# 20240311-sn76489-ver1.net
KiCad netlist of a schematic drawn in EAGLE
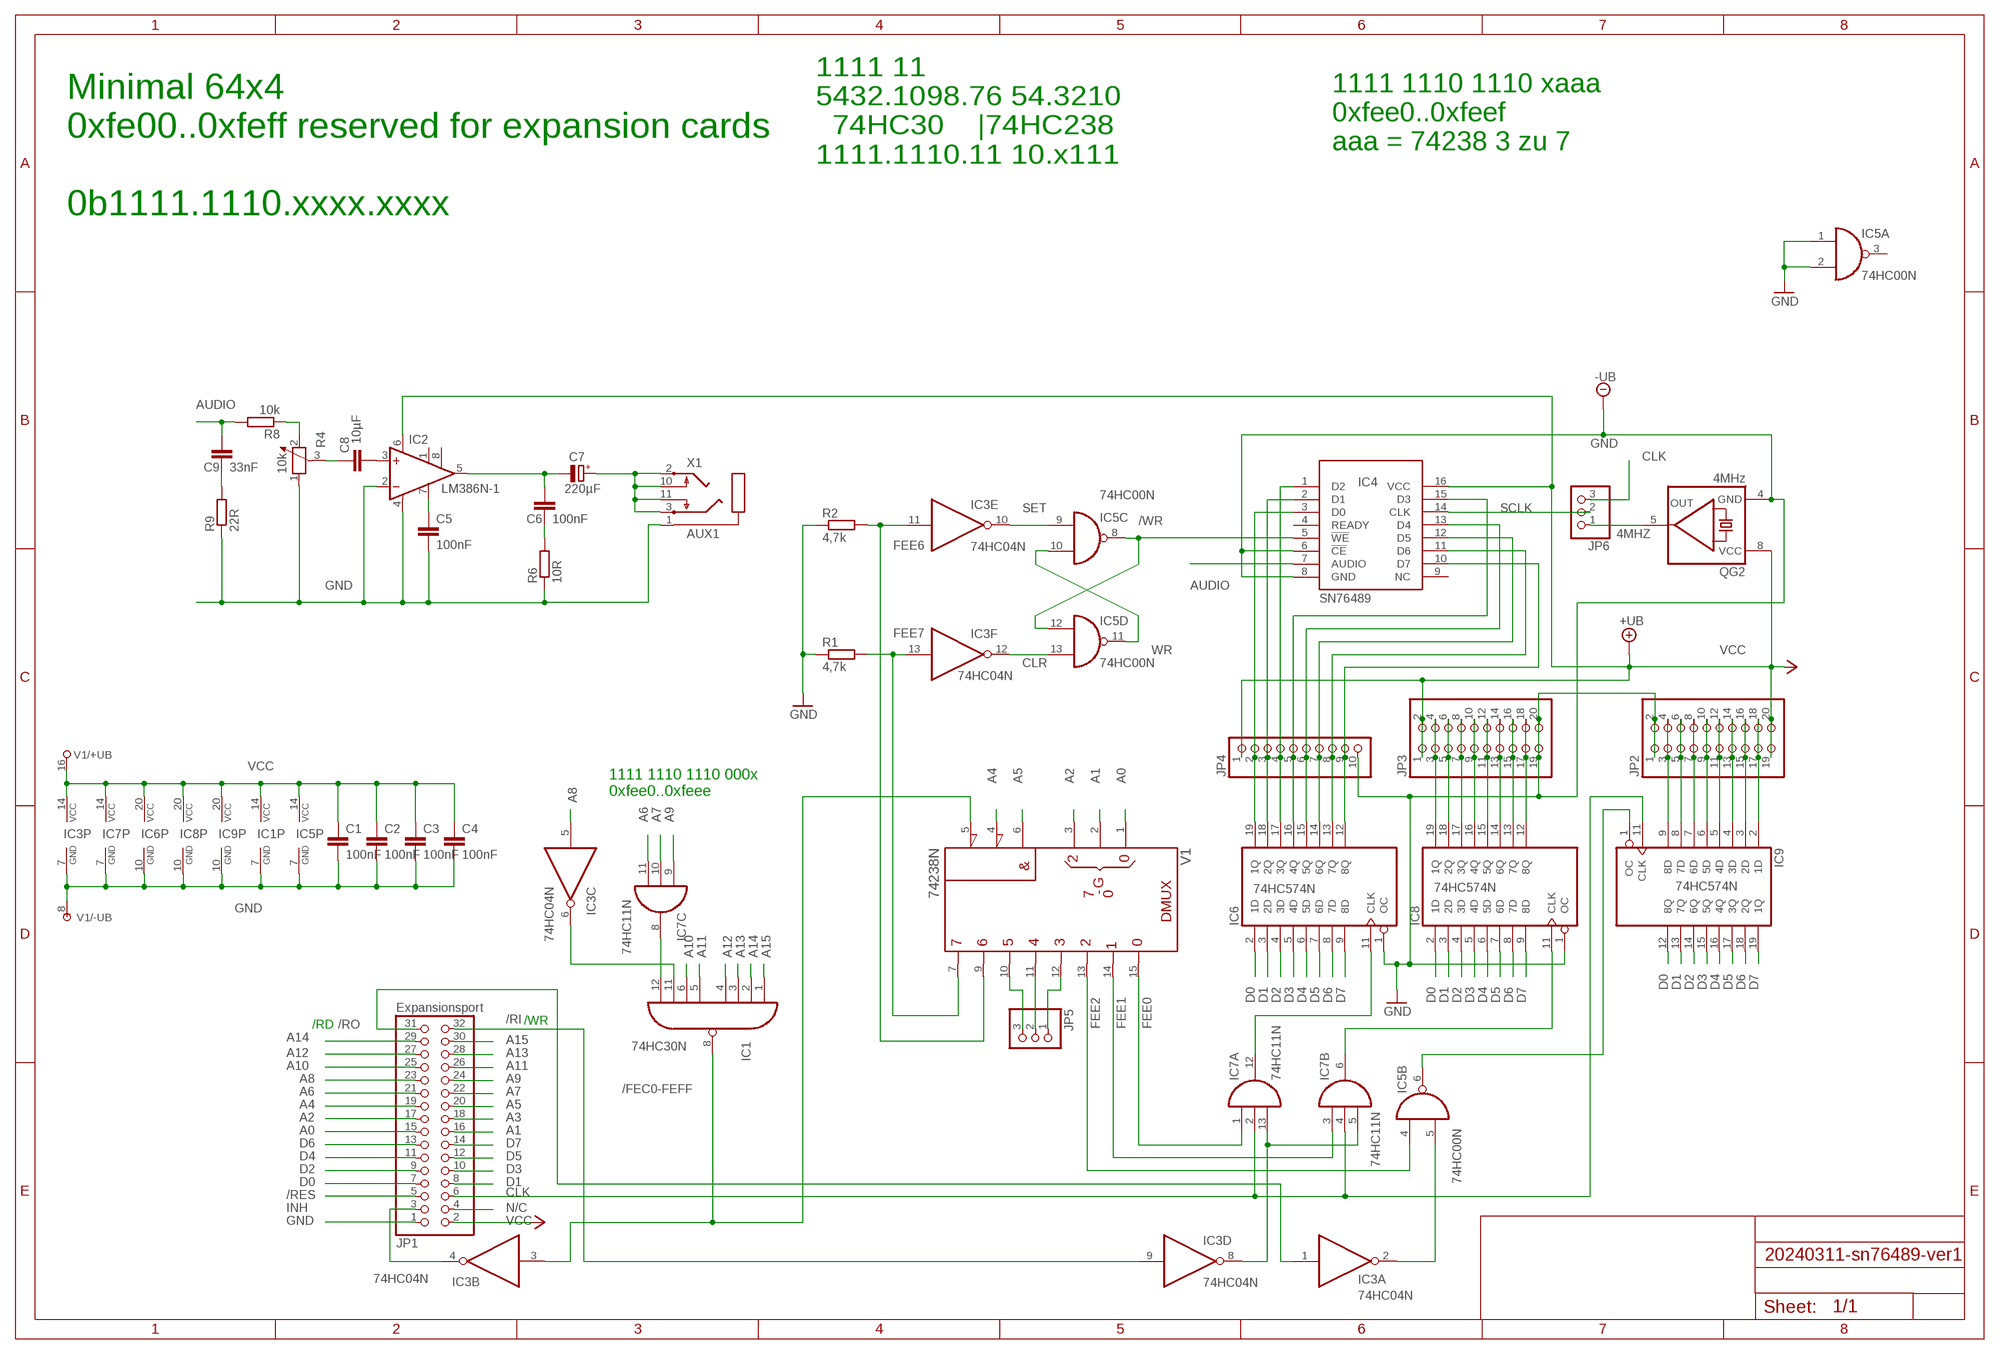
[diagram p0: schematic, sheet 1]

(export (version "E")
  (design (tool "Eeschema 10.0.6"))
  (components
    (comp (ref "C1")
      (value "100nF")
      (footprint "eagle-import:C050-025X075")
      (libsource (lib "eagle-import") (part "C-EU050-025X075"))
    )
    (comp (ref "C2")
      (value "100nF")
      (footprint "eagle-import:C050-025X075")
      (libsource (lib "eagle-import") (part "C-EU050-025X075"))
    )
    (comp (ref "C3")
      (value "100nF")
      (footprint "eagle-import:C050-025X075")
      (libsource (lib "eagle-import") (part "C-EU050-025X075"))
    )
    (comp (ref "C4")
      (value "100nF")
      (footprint "eagle-import:C050-025X075")
      (libsource (lib "eagle-import") (part "C-EU050-025X075"))
    )
    (comp (ref "C5")
      (value "100nF")
      (footprint "eagle-import:C050-025X075")
      (libsource (lib "eagle-import") (part "C-EU050-025X075"))
    )
    (comp (ref "C6")
      (value "100nF")
      (footprint "eagle-import:C050-025X075")
      (libsource (lib "eagle-import") (part "C-EU050-025X075"))
    )
    (comp (ref "C7")
      (value "220µF")
      (footprint "eagle-import:E2,5-7")
      (libsource (lib "eagle-import") (part "CPOL-EUE2.5-7"))
    )
    (comp (ref "C8")
      (value "10µF")
      (footprint "eagle-import:C050-025X075")
      (libsource (lib "eagle-import") (part "C-EU050-025X075"))
    )
    (comp (ref "C9")
      (value "33nF")
      (footprint "eagle-import:C050-025X075")
      (libsource (lib "eagle-import") (part "C-EU050-025X075"))
    )
    (comp (ref "IC1")
      (value "74HC30N")
      (footprint "eagle-import:DIL14")
      (libsource (lib "eagle-import") (part "7430NHC"))
    )
    (comp (ref "IC2")
      (value "LM386N-1")
      (footprint "eagle-import:DIL08")
      (libsource (lib "eagle-import") (part "LM386?-N1"))
    )
    (comp (ref "IC3")
      (value "74HC04N")
      (footprint "eagle-import:DIL14")
      (libsource (lib "eagle-import") (part "7404NHC"))
    )
    (comp (ref "IC4")
      (value "SN76489")
      (footprint "eagle-import:ALEX-PARTS_DIL16")
      (libsource (lib "eagle-import") (part "ALEX-PARTS_SN76489AN"))
    )
    (comp (ref "IC5")
      (value "74HC00N")
      (footprint "eagle-import:DIL14")
      (libsource (lib "eagle-import") (part "7400NHC"))
    )
    (comp (ref "IC6")
      (value "74HC574N")
      (footprint "eagle-import:DIL20")
      (libsource (lib "eagle-import") (part "74574NHC"))
    )
    (comp (ref "IC7")
      (value "74HC11N")
      (footprint "eagle-import:DIL14")
      (libsource (lib "eagle-import") (part "7411NHC"))
    )
    (comp (ref "IC8")
      (value "74HC574N")
      (footprint "eagle-import:DIL20")
      (libsource (lib "eagle-import") (part "74574NHC"))
    )
    (comp (ref "IC9")
      (value "74HC574N")
      (footprint "eagle-import:DIL20")
      (libsource (lib "eagle-import") (part "74574NHC"))
    )
    (comp (ref "JP1")
      (value "Expansionsport")
      (footprint "eagle-import:2X16")
      (libsource (lib "eagle-import") (part "PINHD-2X16"))
    )
    (comp (ref "JP2")
      (value "PINHD-2X10")
      (footprint "eagle-import:2X10")
      (libsource (lib "eagle-import") (part "PINHD-2X10"))
    )
    (comp (ref "JP3")
      (value "PINHD-2X10")
      (footprint "eagle-import:2X10")
      (libsource (lib "eagle-import") (part "PINHD-2X10"))
    )
    (comp (ref "JP4")
      (value "PINHD-1X10")
      (footprint "eagle-import:1X10")
      (libsource (lib "eagle-import") (part "PINHD-1X10"))
    )
    (comp (ref "JP5")
      (value "PINHD-1X3")
      (footprint "eagle-import:1X03")
      (libsource (lib "eagle-import") (part "PINHD-1X3"))
    )
    (comp (ref "JP6")
      (value "PINHD-1X3")
      (footprint "eagle-import:1X03")
      (libsource (lib "eagle-import") (part "PINHD-1X3"))
    )
    (comp (ref "QG2")
      (value "4MHz")
      (footprint "eagle-import:DIL08S")
      (libsource (lib "eagle-import") (part "QG5460"))
    )
    (comp (ref "R1")
      (value "4,7k")
      (footprint "eagle-import:0207_10")
      (libsource (lib "eagle-import") (part "R-EU_0207/10"))
    )
    (comp (ref "R2")
      (value "4,7k")
      (footprint "eagle-import:0207_10")
      (libsource (lib "eagle-import") (part "R-EU_0207/10"))
    )
    (comp (ref "R4")
      (value "10k")
      (footprint "eagle-import:PT-10S")
      (libsource (lib "eagle-import") (part "POTENTIOMETER_PT-10S"))
    )
    (comp (ref "R6")
      (value "10R")
      (footprint "eagle-import:0207_10")
      (libsource (lib "eagle-import") (part "R-EU_0207/10"))
    )
    (comp (ref "R8")
      (value "10k")
      (footprint "eagle-import:0207_10")
      (libsource (lib "eagle-import") (part "R-EU_0207/10"))
    )
    (comp (ref "R9")
      (value "22R")
      (footprint "eagle-import:0207_10")
      (libsource (lib "eagle-import") (part "R-EU_0207/10"))
    )
    (comp (ref "V1")
      (value "74238N")
      (footprint "eagle-import:DIL16")
      (libsource (lib "eagle-import") (part "74238N"))
    )
    (comp (ref "X1")
      (value "AUX1")
      (footprint "eagle-import:SJ1-352XN")
      (libsource (lib "eagle-import") (part "CON-SJ1-352XNSJ1-352XN"))
    )
  )
  (nets
    (net (code "1") (name "+UB") (class "Default")
      (node (ref "C1") (pin "1") (pinfunction "1_1") (pintype "passive"))
      (node (ref "C2") (pin "1") (pinfunction "1_1") (pintype "passive"))
      (node (ref "C3") (pin "1") (pinfunction "1_1") (pintype "passive"))
      (node (ref "C4") (pin "1") (pinfunction "1_1") (pintype "passive"))
      (node (ref "IC1") (pin "14") (pinfunction "VCC_14") (pintype "power_in"))
      (node (ref "IC2") (pin "6") (pinfunction "VS_6") (pintype "power_in"))
      (node (ref "IC3") (pin "14") (pinfunction "VCC_14") (pintype "power_in"))
      (node (ref "IC4") (pin "16") (pinfunction "VCC_16") (pintype "input"))
      (node (ref "IC5") (pin "14") (pinfunction "VCC_14") (pintype "power_in"))
      (node (ref "IC6") (pin "20") (pinfunction "VCC_20") (pintype "power_in"))
      (node (ref "IC7") (pin "14") (pinfunction "VCC_14") (pintype "power_in"))
      (node (ref "IC8") (pin "20") (pinfunction "VCC_20") (pintype "power_in"))
      (node (ref "IC9") (pin "20") (pinfunction "VCC_20") (pintype "power_in"))
      (node (ref "JP1") (pin "2") (pinfunction "2_2") (pintype "passive"))
      (node (ref "JP2") (pin "19") (pinfunction "19_19") (pintype "passive"))
      (node (ref "JP2") (pin "20") (pinfunction "20_20") (pintype "passive"))
      (node (ref "JP3") (pin "1") (pinfunction "1_1") (pintype "passive"))
      (node (ref "JP3") (pin "2") (pinfunction "2_2") (pintype "passive"))
      (node (ref "JP4") (pin "1") (pinfunction "1_1") (pintype "passive"))
      (node (ref "QG2") (pin "8") (pinfunction "VCC_8") (pintype "power_in"))
      (node (ref "V1") (pin "16") (pinfunction "+UB_16") (pintype "power_in"))
    )
    (net (code "2") (name "-UB") (class "Default")
      (node (ref "C1") (pin "2") (pinfunction "2_2") (pintype "passive"))
      (node (ref "C2") (pin "2") (pinfunction "2_2") (pintype "passive"))
      (node (ref "C3") (pin "2") (pinfunction "2_2") (pintype "passive"))
      (node (ref "C4") (pin "2") (pinfunction "2_2") (pintype "passive"))
      (node (ref "C5") (pin "2") (pinfunction "2_2") (pintype "passive"))
      (node (ref "IC1") (pin "7") (pinfunction "GND_7") (pintype "power_in"))
      (node (ref "IC2") (pin "2") (pinfunction "-IN_2") (pintype "input"))
      (node (ref "IC2") (pin "4") (pinfunction "GND_4") (pintype "power_in"))
      (node (ref "IC3") (pin "7") (pinfunction "GND_7") (pintype "power_in"))
      (node (ref "IC4") (pin "6") (pinfunction "~{CE}_6") (pintype "input"))
      (node (ref "IC4") (pin "8") (pinfunction "GND_8") (pintype "power_in"))
      (node (ref "IC5") (pin "1") (pinfunction "I0_1") (pintype "input"))
      (node (ref "IC5") (pin "2") (pinfunction "I1_2") (pintype "input"))
      (node (ref "IC5") (pin "7") (pinfunction "GND_7") (pintype "power_in"))
      (node (ref "IC6") (pin "1") (pinfunction "OC_1") (pintype "input"))
      (node (ref "IC6") (pin "10") (pinfunction "GND_10") (pintype "power_in"))
      (node (ref "IC7") (pin "7") (pinfunction "GND_7") (pintype "power_in"))
      (node (ref "IC8") (pin "1") (pinfunction "OC_1") (pintype "input"))
      (node (ref "IC8") (pin "10") (pinfunction "GND_10") (pintype "power_in"))
      (node (ref "IC9") (pin "10") (pinfunction "GND_10") (pintype "power_in"))
      (node (ref "JP1") (pin "1") (pinfunction "1_1") (pintype "passive"))
      (node (ref "JP2") (pin "1") (pinfunction "1_1") (pintype "passive"))
      (node (ref "JP2") (pin "2") (pinfunction "2_2") (pintype "passive"))
      (node (ref "JP3") (pin "19") (pinfunction "19_19") (pintype "passive"))
      (node (ref "JP3") (pin "20") (pinfunction "20_20") (pintype "passive"))
      (node (ref "JP4") (pin "10") (pinfunction "10_10") (pintype "passive"))
      (node (ref "QG2") (pin "4") (pinfunction "GND_4") (pintype "power_in"))
      (node (ref "R1") (pin "1") (pinfunction "1_1") (pintype "passive"))
      (node (ref "R2") (pin "1") (pinfunction "1_1") (pintype "passive"))
      (node (ref "R4") (pin "1") (pinfunction "1_1") (pintype "passive"))
      (node (ref "R6") (pin "1") (pinfunction "1_1") (pintype "passive"))
      (node (ref "R9") (pin "1") (pinfunction "1_1") (pintype "passive"))
      (node (ref "V1") (pin "8") (pinfunction "-UB_8") (pintype "power_in"))
      (node (ref "X1") (pin "1") (pinfunction "1_1") (pintype "passive"))
    )
    (net (code "3") (name "/4MHZ") (class "Default")
      (node (ref "JP6") (pin "1") (pinfunction "1_1") (pintype "passive"))
      (node (ref "QG2") (pin "5") (pinfunction "OUT_5") (pintype "output"))
    )
    (net (code "4") (name "/A0") (class "Default")
      (node (ref "JP1") (pin "15") (pinfunction "15_15") (pintype "passive"))
      (node (ref "V1") (pin "1") (pinfunction "A_1") (pintype "input"))
    )
    (net (code "5") (name "/A1") (class "Default")
      (node (ref "JP1") (pin "16") (pinfunction "16_16") (pintype "passive"))
      (node (ref "V1") (pin "2") (pinfunction "B_2") (pintype "input"))
    )
    (net (code "6") (name "/A2") (class "Default")
      (node (ref "JP1") (pin "17") (pinfunction "17_17") (pintype "passive"))
      (node (ref "V1") (pin "3") (pinfunction "C_3") (pintype "input"))
    )
    (net (code "7") (name "/A3") (class "Default")
      (node (ref "JP1") (pin "18") (pinfunction "18_18") (pintype "passive"))
    )
    (net (code "8") (name "/A4") (class "Default")
      (node (ref "JP1") (pin "19") (pinfunction "19_19") (pintype "passive"))
      (node (ref "V1") (pin "4") (pinfunction "~{G2A}_4") (pintype "input"))
    )
    (net (code "9") (name "/A5") (class "Default")
      (node (ref "JP1") (pin "20") (pinfunction "20_20") (pintype "passive"))
      (node (ref "V1") (pin "6") (pinfunction "G1_6") (pintype "input"))
    )
    (net (code "10") (name "/A6") (class "Default")
      (node (ref "IC7") (pin "11") (pinfunction "I2_11") (pintype "input"))
      (node (ref "JP1") (pin "21") (pinfunction "21_21") (pintype "passive"))
    )
    (net (code "11") (name "/A7") (class "Default")
      (node (ref "IC7") (pin "10") (pinfunction "I1_10") (pintype "input"))
      (node (ref "JP1") (pin "22") (pinfunction "22_22") (pintype "passive"))
    )
    (net (code "12") (name "/A8") (class "Default")
      (node (ref "IC3") (pin "5") (pinfunction "I_5") (pintype "input"))
      (node (ref "JP1") (pin "23") (pinfunction "23_23") (pintype "passive"))
    )
    (net (code "13") (name "/A9") (class "Default")
      (node (ref "IC7") (pin "9") (pinfunction "I0_9") (pintype "input"))
      (node (ref "JP1") (pin "24") (pinfunction "24_24") (pintype "passive"))
    )
    (net (code "14") (name "/A10") (class "Default")
      (node (ref "IC1") (pin "6") (pinfunction "I5_6") (pintype "input"))
      (node (ref "JP1") (pin "25") (pinfunction "25_25") (pintype "passive"))
    )
    (net (code "15") (name "/A11") (class "Default")
      (node (ref "IC1") (pin "5") (pinfunction "I4_5") (pintype "input"))
      (node (ref "JP1") (pin "26") (pinfunction "26_26") (pintype "passive"))
    )
    (net (code "16") (name "/A12") (class "Default")
      (node (ref "IC1") (pin "4") (pinfunction "I3_4") (pintype "input"))
      (node (ref "JP1") (pin "27") (pinfunction "27_27") (pintype "passive"))
    )
    (net (code "17") (name "/A13") (class "Default")
      (node (ref "IC1") (pin "3") (pinfunction "I2_3") (pintype "input"))
      (node (ref "JP1") (pin "28") (pinfunction "28_28") (pintype "passive"))
    )
    (net (code "18") (name "/A14") (class "Default")
      (node (ref "IC1") (pin "2") (pinfunction "I1_2") (pintype "input"))
      (node (ref "JP1") (pin "29") (pinfunction "29_29") (pintype "passive"))
    )
    (net (code "19") (name "/A15") (class "Default")
      (node (ref "IC1") (pin "1") (pinfunction "I0_1") (pintype "input"))
      (node (ref "JP1") (pin "30") (pinfunction "30_30") (pintype "passive"))
    )
    (net (code "20") (name "/AUDIO") (class "Default")
      (node (ref "C9") (pin "1") (pinfunction "1_1") (pintype "passive"))
      (node (ref "IC4") (pin "7") (pinfunction "AUDIO_7") (pintype "output"))
      (node (ref "R8") (pin "2") (pinfunction "2_2") (pintype "passive"))
    )
    (net (code "21") (name "/CLK") (class "Default")
      (node (ref "IC7") (pin "2") (pinfunction "I1_2") (pintype "input"))
      (node (ref "IC7") (pin "4") (pinfunction "I1_4") (pintype "input"))
      (node (ref "IC9") (pin "11") (pinfunction "CLK_11") (pintype "input"))
      (node (ref "JP1") (pin "6") (pinfunction "6_6") (pintype "passive"))
      (node (ref "JP6") (pin "3") (pinfunction "3_3") (pintype "passive"))
    )
    (net (code "22") (name "/CLR") (class "Default")
      (node (ref "IC3") (pin "12") (pinfunction "O_12") (pintype "output"))
      (node (ref "IC5") (pin "13") (pinfunction "I1_13") (pintype "input"))
    )
    (net (code "23") (name "/D0") (class "Default")
      (node (ref "IC6") (pin "2") (pinfunction "1D_2") (pintype "input"))
      (node (ref "IC8") (pin "2") (pinfunction "1D_2") (pintype "input"))
      (node (ref "IC9") (pin "12") (pinfunction "8Q_12") (pintype "tri_state"))
      (node (ref "JP1") (pin "7") (pinfunction "7_7") (pintype "passive"))
    )
    (net (code "24") (name "/D1") (class "Default")
      (node (ref "IC6") (pin "3") (pinfunction "2D_3") (pintype "input"))
      (node (ref "IC8") (pin "3") (pinfunction "2D_3") (pintype "input"))
      (node (ref "IC9") (pin "13") (pinfunction "7Q_13") (pintype "tri_state"))
      (node (ref "JP1") (pin "8") (pinfunction "8_8") (pintype "passive"))
    )
    (net (code "25") (name "/D2") (class "Default")
      (node (ref "IC6") (pin "4") (pinfunction "3D_4") (pintype "input"))
      (node (ref "IC8") (pin "4") (pinfunction "3D_4") (pintype "input"))
      (node (ref "IC9") (pin "14") (pinfunction "6Q_14") (pintype "tri_state"))
      (node (ref "JP1") (pin "9") (pinfunction "9_9") (pintype "passive"))
    )
    (net (code "26") (name "/D3") (class "Default")
      (node (ref "IC6") (pin "5") (pinfunction "4D_5") (pintype "input"))
      (node (ref "IC8") (pin "5") (pinfunction "4D_5") (pintype "input"))
      (node (ref "IC9") (pin "15") (pinfunction "5Q_15") (pintype "tri_state"))
      (node (ref "JP1") (pin "10") (pinfunction "10_10") (pintype "passive"))
    )
    (net (code "27") (name "/D4") (class "Default")
      (node (ref "IC6") (pin "6") (pinfunction "5D_6") (pintype "input"))
      (node (ref "IC8") (pin "6") (pinfunction "5D_6") (pintype "input"))
      (node (ref "IC9") (pin "16") (pinfunction "4Q_16") (pintype "tri_state"))
      (node (ref "JP1") (pin "11") (pinfunction "11_11") (pintype "passive"))
    )
    (net (code "28") (name "/D5") (class "Default")
      (node (ref "IC6") (pin "7") (pinfunction "6D_7") (pintype "input"))
      (node (ref "IC8") (pin "7") (pinfunction "6D_7") (pintype "input"))
      (node (ref "IC9") (pin "17") (pinfunction "3Q_17") (pintype "tri_state"))
      (node (ref "JP1") (pin "12") (pinfunction "12_12") (pintype "passive"))
    )
    (net (code "29") (name "/D6") (class "Default")
      (node (ref "IC6") (pin "8") (pinfunction "7D_8") (pintype "input"))
      (node (ref "IC8") (pin "8") (pinfunction "7D_8") (pintype "input"))
      (node (ref "IC9") (pin "18") (pinfunction "2Q_18") (pintype "tri_state"))
      (node (ref "JP1") (pin "13") (pinfunction "13_13") (pintype "passive"))
    )
    (net (code "30") (name "/D7") (class "Default")
      (node (ref "IC6") (pin "9") (pinfunction "8D_9") (pintype "input"))
      (node (ref "IC8") (pin "9") (pinfunction "8D_9") (pintype "input"))
      (node (ref "IC9") (pin "19") (pinfunction "1Q_19") (pintype "tri_state"))
      (node (ref "JP1") (pin "14") (pinfunction "14_14") (pintype "passive"))
    )
    (net (code "31") (name "/FEE0") (class "Default")
      (node (ref "IC7") (pin "1") (pinfunction "I0_1") (pintype "input"))
      (node (ref "V1") (pin "15") (pinfunction "Y0_15") (pintype "output"))
    )
    (net (code "32") (name "/FEE1") (class "Default")
      (node (ref "IC7") (pin "3") (pinfunction "I0_3") (pintype "input"))
      (node (ref "V1") (pin "14") (pinfunction "Y1_14") (pintype "output"))
    )
    (net (code "33") (name "/FEE2") (class "Default")
      (node (ref "IC5") (pin "4") (pinfunction "I0_4") (pintype "input"))
      (node (ref "V1") (pin "13") (pinfunction "Y2_13") (pintype "output"))
    )
    (net (code "34") (name "/FEE6") (class "Default")
      (node (ref "IC3") (pin "11") (pinfunction "I_11") (pintype "input"))
      (node (ref "R2") (pin "2") (pinfunction "2_2") (pintype "passive"))
      (node (ref "V1") (pin "9") (pinfunction "Y6_9") (pintype "output"))
    )
    (net (code "35") (name "/FEE7") (class "Default")
      (node (ref "IC3") (pin "13") (pinfunction "I_13") (pintype "input"))
      (node (ref "R1") (pin "2") (pinfunction "2_2") (pintype "passive"))
      (node (ref "V1") (pin "7") (pinfunction "Y7_7") (pintype "output"))
    )
    (net (code "36") (name "/INH") (class "Default")
      (node (ref "IC3") (pin "4") (pinfunction "O_4") (pintype "output"))
      (node (ref "JP1") (pin "3") (pinfunction "3_3") (pintype "passive"))
    )
    (net (code "37") (name "/N{slash}C") (class "Default")
      (node (ref "JP1") (pin "4") (pinfunction "4_4") (pintype "passive"))
    )
    (net (code "38") (name "/SCLK") (class "Default")
      (node (ref "IC4") (pin "14") (pinfunction "CLK_14") (pintype "input"))
      (node (ref "JP6") (pin "2") (pinfunction "2_2") (pintype "passive"))
    )
    (net (code "39") (name "/SET") (class "Default")
      (node (ref "IC3") (pin "10") (pinfunction "O_10") (pintype "output"))
      (node (ref "IC5") (pin "9") (pinfunction "I0_9") (pintype "input"))
    )
    (net (code "40") (name "/WR") (class "Default")
      (node (ref "IC5") (pin "10") (pinfunction "I1_10") (pintype "input"))
      (node (ref "IC5") (pin "11") (pinfunction "O_11") (pintype "output"))
    )
    (net (code "41") (name "/{slash}FEC0-FEFF") (class "Default")
      (node (ref "IC1") (pin "8") (pinfunction "O_8") (pintype "output"))
      (node (ref "IC3") (pin "3") (pinfunction "I_3") (pintype "input"))
      (node (ref "V1") (pin "5") (pinfunction "~{G2B}_5") (pintype "input"))
    )
    (net (code "42") (name "/{slash}RES") (class "Default")
      (node (ref "JP1") (pin "5") (pinfunction "5_5") (pintype "passive"))
    )
    (net (code "43") (name "/{slash}RI") (class "Default")
      (node (ref "IC3") (pin "9") (pinfunction "I_9") (pintype "input"))
      (node (ref "JP1") (pin "32") (pinfunction "32_32") (pintype "passive"))
    )
    (net (code "44") (name "/{slash}RO") (class "Default")
      (node (ref "IC3") (pin "1") (pinfunction "I_1") (pintype "input"))
      (node (ref "JP1") (pin "31") (pinfunction "31_31") (pintype "passive"))
    )
    (net (code "45") (name "/{slash}WR") (class "Default")
      (node (ref "IC4") (pin "5") (pinfunction "~{WE}_5") (pintype "input"))
      (node (ref "IC5") (pin "12") (pinfunction "I0_12") (pintype "input"))
      (node (ref "IC5") (pin "8") (pinfunction "O_8") (pintype "output"))
    )
    (net (code "46") (name "Net-(C6-Pad2)") (class "Default")
      (node (ref "C6") (pin "2") (pinfunction "2_2") (pintype "passive"))
      (node (ref "R6") (pin "2") (pinfunction "2_2") (pintype "passive"))
    )
    (net (code "47") (name "Net-(C7-Pad+)") (class "Default")
      (node (ref "C7") (pin "+") (pinfunction "+_+") (pintype "passive"))
      (node (ref "X1") (pin "10") (pinfunction "10_10") (pintype "passive"))
      (node (ref "X1") (pin "11") (pinfunction "11_11") (pintype "passive"))
      (node (ref "X1") (pin "2") (pinfunction "2_2") (pintype "passive"))
      (node (ref "X1") (pin "3") (pinfunction "3_3") (pintype "passive"))
    )
    (net (code "48") (name "Net-(C8-Pad1)") (class "Default")
      (node (ref "C8") (pin "1") (pinfunction "1_1") (pintype "passive"))
      (node (ref "R4") (pin "3") (pinfunction "3_3") (pintype "passive"))
    )
    (net (code "49") (name "Net-(C9-Pad2)") (class "Default")
      (node (ref "C9") (pin "2") (pinfunction "2_2") (pintype "passive"))
      (node (ref "R9") (pin "2") (pinfunction "2_2") (pintype "passive"))
    )
    (net (code "50") (name "Net-(IC1A-I6)") (class "Default")
      (node (ref "IC1") (pin "11") (pinfunction "I6_11") (pintype "input"))
      (node (ref "IC3") (pin "6") (pinfunction "O_6") (pintype "output"))
    )
    (net (code "51") (name "Net-(IC1A-I7)") (class "Default")
      (node (ref "IC1") (pin "12") (pinfunction "I7_12") (pintype "input"))
      (node (ref "IC7") (pin "8") (pinfunction "O_8") (pintype "output"))
    )
    (net (code "52") (name "Net-(IC2-+IN)") (class "Default")
      (node (ref "C8") (pin "2") (pinfunction "2_2") (pintype "passive"))
      (node (ref "IC2") (pin "3") (pinfunction "+IN_3") (pintype "input"))
    )
    (net (code "53") (name "Net-(IC2-BYPASS)") (class "Default")
      (node (ref "C5") (pin "1") (pinfunction "1_1") (pintype "passive"))
      (node (ref "IC2") (pin "7") (pinfunction "BYPASS_7") (pintype "passive"))
    )
    (net (code "54") (name "Net-(IC2-OUT)") (class "Default")
      (node (ref "C6") (pin "1") (pinfunction "1_1") (pintype "passive"))
      (node (ref "C7") (pin "-") (pinfunction "-_-") (pintype "passive"))
      (node (ref "IC2") (pin "5") (pinfunction "OUT_5") (pintype "output"))
    )
    (net (code "55") (name "Net-(IC3A-O)") (class "Default")
      (node (ref "IC3") (pin "2") (pinfunction "O_2") (pintype "output"))
      (node (ref "IC5") (pin "5") (pinfunction "I1_5") (pintype "input"))
    )
    (net (code "56") (name "Net-(IC3D-O)") (class "Default")
      (node (ref "IC3") (pin "8") (pinfunction "O_8") (pintype "output"))
      (node (ref "IC7") (pin "13") (pinfunction "I2_13") (pintype "input"))
      (node (ref "IC7") (pin "5") (pinfunction "I2_5") (pintype "input"))
    )
    (net (code "57") (name "Net-(IC4-D0)") (class "Default")
      (node (ref "IC4") (pin "3") (pinfunction "D0_3") (pintype "input"))
      (node (ref "IC6") (pin "19") (pinfunction "1Q_19") (pintype "tri_state"))
      (node (ref "JP4") (pin "2") (pinfunction "2_2") (pintype "passive"))
    )
    (net (code "58") (name "Net-(IC4-D1)") (class "Default")
      (node (ref "IC4") (pin "2") (pinfunction "D1_2") (pintype "input"))
      (node (ref "IC6") (pin "18") (pinfunction "2Q_18") (pintype "tri_state"))
      (node (ref "JP4") (pin "3") (pinfunction "3_3") (pintype "passive"))
    )
    (net (code "59") (name "Net-(IC4-D2)") (class "Default")
      (node (ref "IC4") (pin "1") (pinfunction "D2_1") (pintype "input"))
      (node (ref "IC6") (pin "17") (pinfunction "3Q_17") (pintype "tri_state"))
      (node (ref "JP4") (pin "4") (pinfunction "4_4") (pintype "passive"))
    )
    (net (code "60") (name "Net-(IC4-D3)") (class "Default")
      (node (ref "IC4") (pin "15") (pinfunction "D3_15") (pintype "input"))
      (node (ref "IC6") (pin "16") (pinfunction "4Q_16") (pintype "tri_state"))
      (node (ref "JP4") (pin "5") (pinfunction "5_5") (pintype "passive"))
    )
    (net (code "61") (name "Net-(IC4-D4)") (class "Default")
      (node (ref "IC4") (pin "13") (pinfunction "D4_13") (pintype "input"))
      (node (ref "IC6") (pin "15") (pinfunction "5Q_15") (pintype "tri_state"))
      (node (ref "JP4") (pin "6") (pinfunction "6_6") (pintype "passive"))
    )
    (net (code "62") (name "Net-(IC4-D5)") (class "Default")
      (node (ref "IC4") (pin "12") (pinfunction "D5_12") (pintype "input"))
      (node (ref "IC6") (pin "14") (pinfunction "6Q_14") (pintype "tri_state"))
      (node (ref "JP4") (pin "7") (pinfunction "7_7") (pintype "passive"))
    )
    (net (code "63") (name "Net-(IC4-D6)") (class "Default")
      (node (ref "IC4") (pin "11") (pinfunction "D6_11") (pintype "input"))
      (node (ref "IC6") (pin "13") (pinfunction "7Q_13") (pintype "tri_state"))
      (node (ref "JP4") (pin "8") (pinfunction "8_8") (pintype "passive"))
    )
    (net (code "64") (name "Net-(IC4-D7)") (class "Default")
      (node (ref "IC4") (pin "10") (pinfunction "D7_10") (pintype "input"))
      (node (ref "IC6") (pin "12") (pinfunction "8Q_12") (pintype "tri_state"))
      (node (ref "JP4") (pin "9") (pinfunction "9_9") (pintype "passive"))
    )
    (net (code "65") (name "Net-(IC5B-O)") (class "Default")
      (node (ref "IC5") (pin "6") (pinfunction "O_6") (pintype "output"))
      (node (ref "IC9") (pin "1") (pinfunction "OC_1") (pintype "input"))
    )
    (net (code "66") (name "Net-(IC6A-CLK)") (class "Default")
      (node (ref "IC6") (pin "11") (pinfunction "CLK_11") (pintype "input"))
      (node (ref "IC7") (pin "12") (pinfunction "O_12") (pintype "output"))
    )
    (net (code "67") (name "Net-(IC7B-O)") (class "Default")
      (node (ref "IC7") (pin "6") (pinfunction "O_6") (pintype "output"))
      (node (ref "IC8") (pin "11") (pinfunction "CLK_11") (pintype "input"))
    )
    (net (code "68") (name "Net-(IC8A-1Q)") (class "Default")
      (node (ref "IC8") (pin "19") (pinfunction "1Q_19") (pintype "tri_state"))
      (node (ref "JP3") (pin "3") (pinfunction "3_3") (pintype "passive"))
      (node (ref "JP3") (pin "4") (pinfunction "4_4") (pintype "passive"))
    )
    (net (code "69") (name "Net-(IC8A-2Q)") (class "Default")
      (node (ref "IC8") (pin "18") (pinfunction "2Q_18") (pintype "tri_state"))
      (node (ref "JP3") (pin "5") (pinfunction "5_5") (pintype "passive"))
      (node (ref "JP3") (pin "6") (pinfunction "6_6") (pintype "passive"))
    )
    (net (code "70") (name "Net-(IC8A-3Q)") (class "Default")
      (node (ref "IC8") (pin "17") (pinfunction "3Q_17") (pintype "tri_state"))
      (node (ref "JP3") (pin "7") (pinfunction "7_7") (pintype "passive"))
      (node (ref "JP3") (pin "8") (pinfunction "8_8") (pintype "passive"))
    )
    (net (code "71") (name "Net-(IC8A-4Q)") (class "Default")
      (node (ref "IC8") (pin "16") (pinfunction "4Q_16") (pintype "tri_state"))
      (node (ref "JP3") (pin "10") (pinfunction "10_10") (pintype "passive"))
      (node (ref "JP3") (pin "9") (pinfunction "9_9") (pintype "passive"))
    )
    (net (code "72") (name "Net-(IC8A-5Q)") (class "Default")
      (node (ref "IC8") (pin "15") (pinfunction "5Q_15") (pintype "tri_state"))
      (node (ref "JP3") (pin "11") (pinfunction "11_11") (pintype "passive"))
      (node (ref "JP3") (pin "12") (pinfunction "12_12") (pintype "passive"))
    )
    (net (code "73") (name "Net-(IC8A-6Q)") (class "Default")
      (node (ref "IC8") (pin "14") (pinfunction "6Q_14") (pintype "tri_state"))
      (node (ref "JP3") (pin "13") (pinfunction "13_13") (pintype "passive"))
      (node (ref "JP3") (pin "14") (pinfunction "14_14") (pintype "passive"))
    )
    (net (code "74") (name "Net-(IC8A-7Q)") (class "Default")
      (node (ref "IC8") (pin "13") (pinfunction "7Q_13") (pintype "tri_state"))
      (node (ref "JP3") (pin "15") (pinfunction "15_15") (pintype "passive"))
      (node (ref "JP3") (pin "16") (pinfunction "16_16") (pintype "passive"))
    )
    (net (code "75") (name "Net-(IC8A-8Q)") (class "Default")
      (node (ref "IC8") (pin "12") (pinfunction "8Q_12") (pintype "tri_state"))
      (node (ref "JP3") (pin "17") (pinfunction "17_17") (pintype "passive"))
      (node (ref "JP3") (pin "18") (pinfunction "18_18") (pintype "passive"))
    )
    (net (code "76") (name "Net-(IC9A-1D)") (class "Default")
      (node (ref "IC9") (pin "2") (pinfunction "1D_2") (pintype "input"))
      (node (ref "JP2") (pin "17") (pinfunction "17_17") (pintype "passive"))
      (node (ref "JP2") (pin "18") (pinfunction "18_18") (pintype "passive"))
    )
    (net (code "77") (name "Net-(IC9A-2D)") (class "Default")
      (node (ref "IC9") (pin "3") (pinfunction "2D_3") (pintype "input"))
      (node (ref "JP2") (pin "15") (pinfunction "15_15") (pintype "passive"))
      (node (ref "JP2") (pin "16") (pinfunction "16_16") (pintype "passive"))
    )
    (net (code "78") (name "Net-(IC9A-3D)") (class "Default")
      (node (ref "IC9") (pin "4") (pinfunction "3D_4") (pintype "input"))
      (node (ref "JP2") (pin "13") (pinfunction "13_13") (pintype "passive"))
      (node (ref "JP2") (pin "14") (pinfunction "14_14") (pintype "passive"))
    )
    (net (code "79") (name "Net-(IC9A-4D)") (class "Default")
      (node (ref "IC9") (pin "5") (pinfunction "4D_5") (pintype "input"))
      (node (ref "JP2") (pin "11") (pinfunction "11_11") (pintype "passive"))
      (node (ref "JP2") (pin "12") (pinfunction "12_12") (pintype "passive"))
    )
    (net (code "80") (name "Net-(IC9A-5D)") (class "Default")
      (node (ref "IC9") (pin "6") (pinfunction "5D_6") (pintype "input"))
      (node (ref "JP2") (pin "10") (pinfunction "10_10") (pintype "passive"))
      (node (ref "JP2") (pin "9") (pinfunction "9_9") (pintype "passive"))
    )
    (net (code "81") (name "Net-(IC9A-6D)") (class "Default")
      (node (ref "IC9") (pin "7") (pinfunction "6D_7") (pintype "input"))
      (node (ref "JP2") (pin "7") (pinfunction "7_7") (pintype "passive"))
      (node (ref "JP2") (pin "8") (pinfunction "8_8") (pintype "passive"))
    )
    (net (code "82") (name "Net-(IC9A-7D)") (class "Default")
      (node (ref "IC9") (pin "8") (pinfunction "7D_8") (pintype "input"))
      (node (ref "JP2") (pin "5") (pinfunction "5_5") (pintype "passive"))
      (node (ref "JP2") (pin "6") (pinfunction "6_6") (pintype "passive"))
    )
    (net (code "83") (name "Net-(IC9A-8D)") (class "Default")
      (node (ref "IC9") (pin "9") (pinfunction "8D_9") (pintype "input"))
      (node (ref "JP2") (pin "3") (pinfunction "3_3") (pintype "passive"))
      (node (ref "JP2") (pin "4") (pinfunction "4_4") (pintype "passive"))
    )
    (net (code "84") (name "Net-(R4-Pad2)") (class "Default")
      (node (ref "R4") (pin "2") (pinfunction "2_2") (pintype "passive"))
      (node (ref "R8") (pin "1") (pinfunction "1_1") (pintype "passive"))
    )
    (net (code "85") (name "Net-(V1C-Y3)") (class "Default")
      (node (ref "JP5") (pin "1") (pinfunction "1_1") (pintype "passive"))
      (node (ref "V1") (pin "12") (pinfunction "Y3_12") (pintype "output"))
    )
    (net (code "86") (name "Net-(V1C-Y4)") (class "Default")
      (node (ref "JP5") (pin "2") (pinfunction "2_2") (pintype "passive"))
      (node (ref "V1") (pin "11") (pinfunction "Y4_11") (pintype "output"))
    )
    (net (code "87") (name "Net-(V1C-Y5)") (class "Default")
      (node (ref "JP5") (pin "3") (pinfunction "3_3") (pintype "passive"))
      (node (ref "V1") (pin "10") (pinfunction "Y5_10") (pintype "output"))
    )
    (net (code "88") (name "unconnected-(IC2-GAIN-Pad1)") (class "Default")
      (node (ref "IC2") (pin "1") (pinfunction "GAIN_1") (pintype "passive"))
    )
    (net (code "89") (name "unconnected-(IC2-GAIN-Pad8)") (class "Default")
      (node (ref "IC2") (pin "8") (pinfunction "GAIN_8") (pintype "passive"))
    )
    (net (code "90") (name "unconnected-(IC4-NC-Pad9)") (class "Default")
      (node (ref "IC4") (pin "9") (pinfunction "NC_9") (pintype "no_connect"))
    )
    (net (code "91") (name "unconnected-(IC4-READY-Pad4)") (class "Default")
      (node (ref "IC4") (pin "4") (pinfunction "READY_4") (pintype "output"))
    )
    (net (code "92") (name "unconnected-(IC5A-O-Pad3)") (class "Default")
      (node (ref "IC5") (pin "3") (pinfunction "O_3") (pintype "output"))
    )
  )
)
